# DorMouse.net
KiCad netlist of a schematic drawn in EAGLE
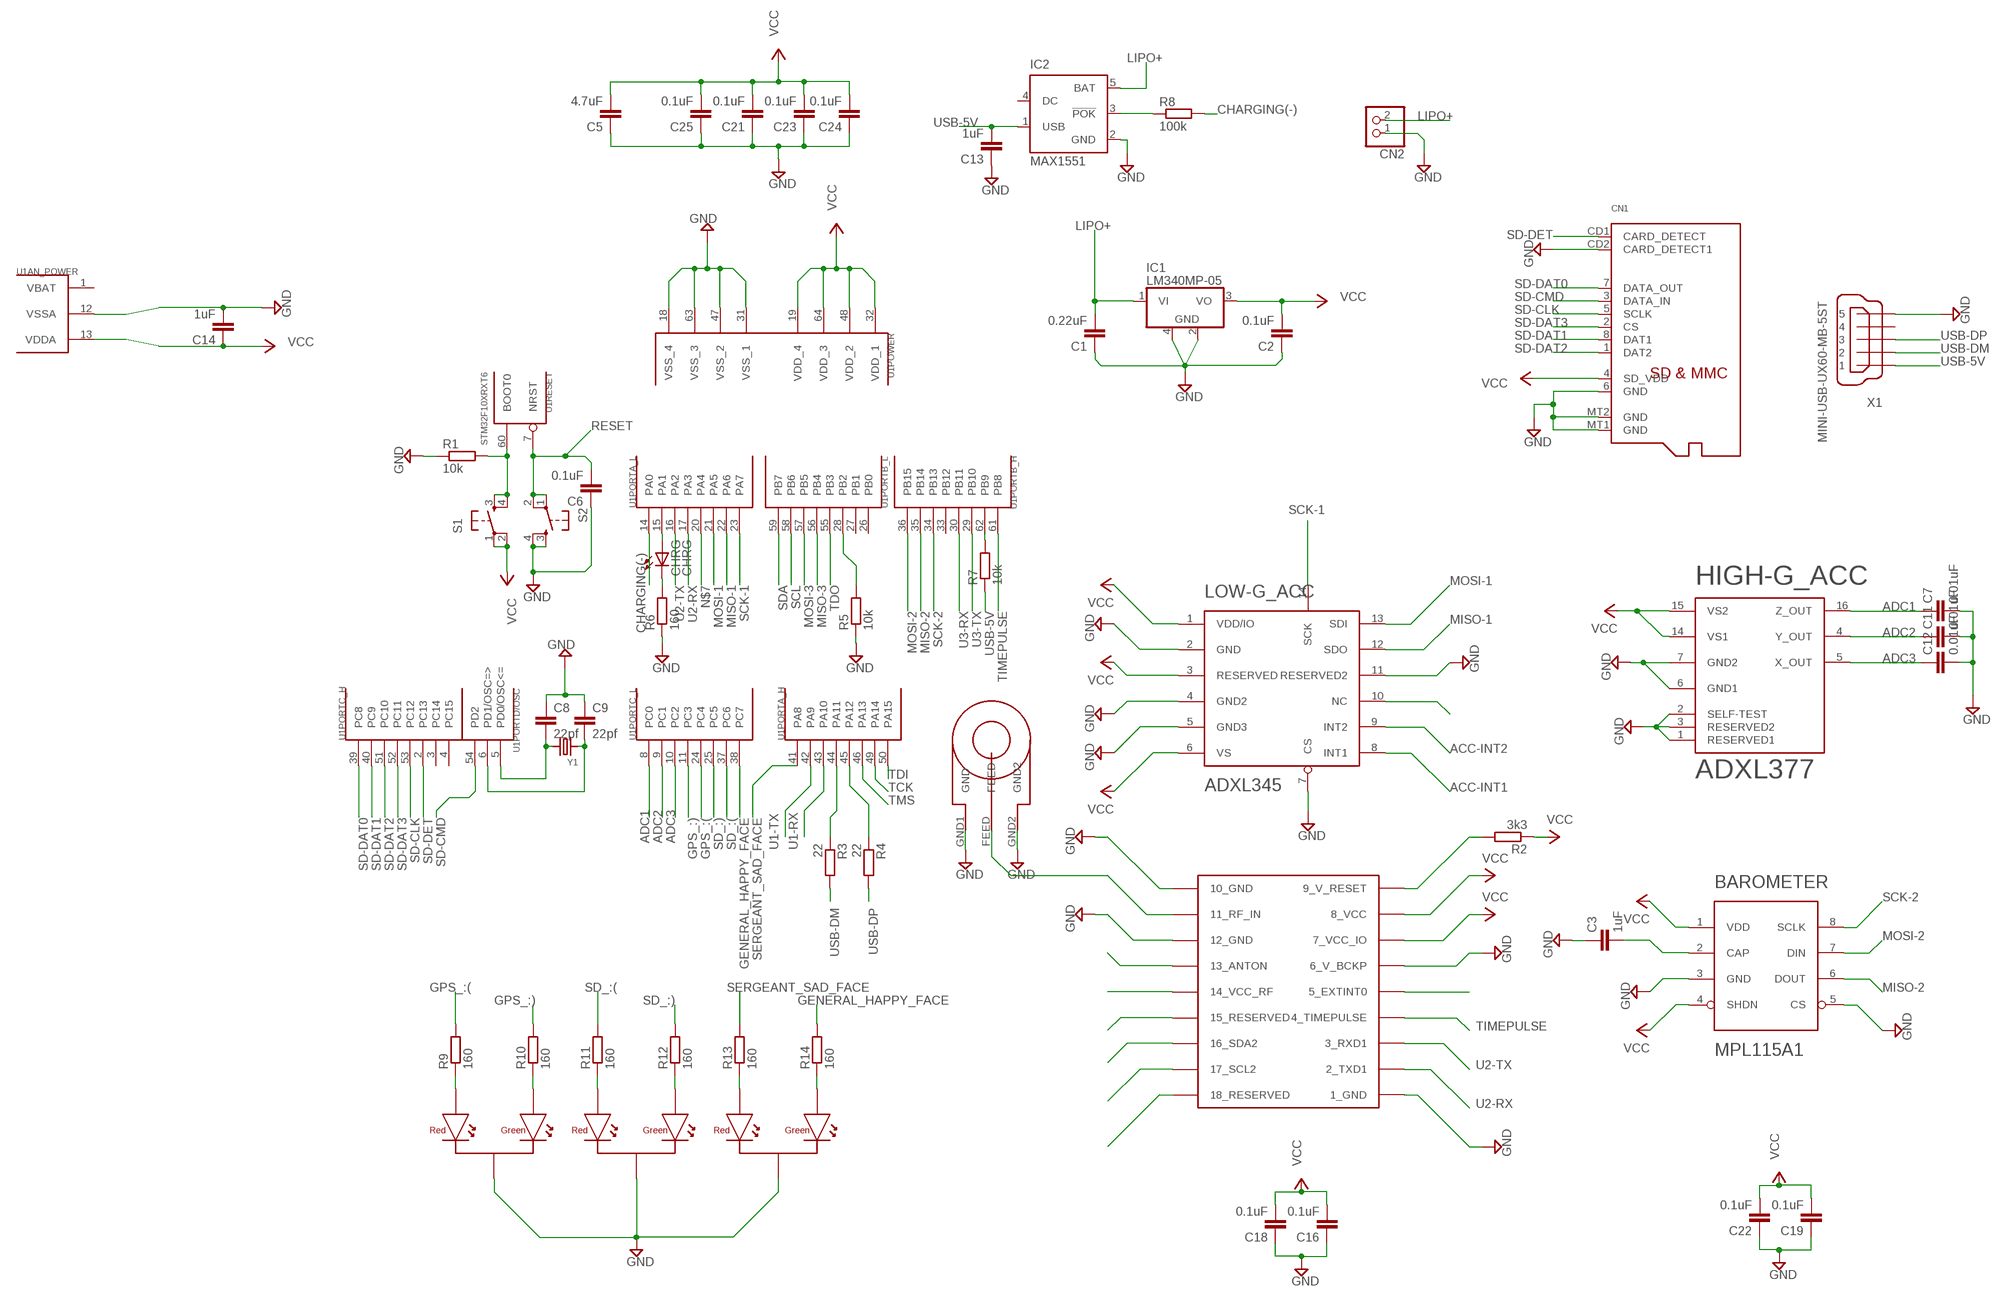
[diagram p0: schematic, sheet 1, part 1 of 2]
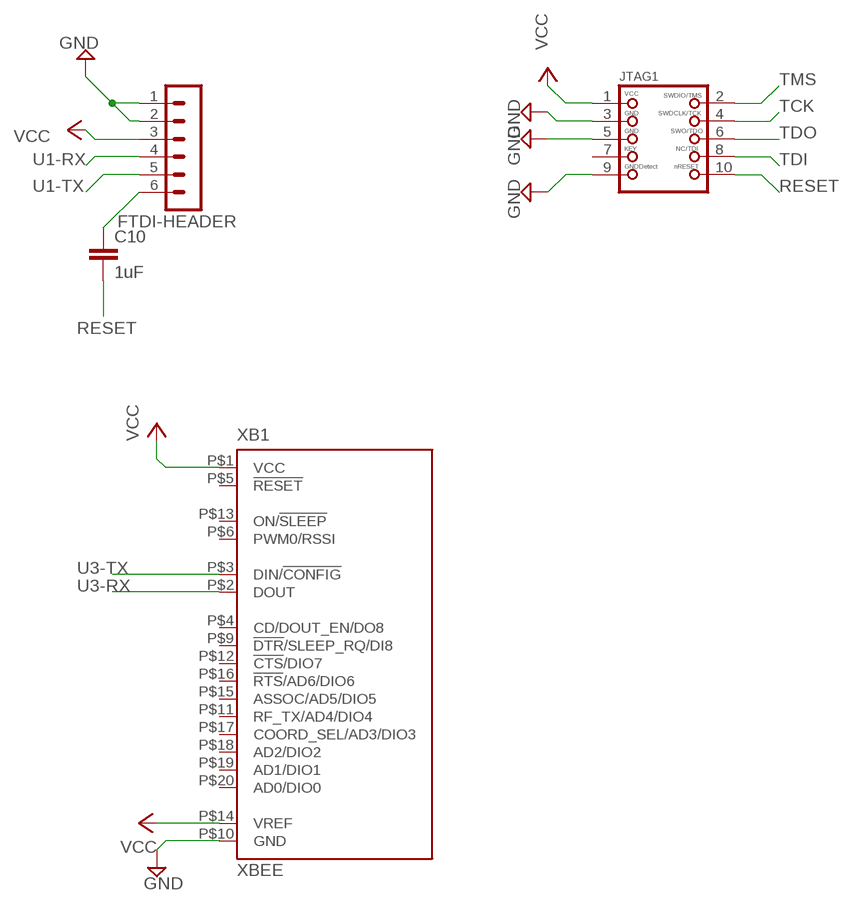
[diagram p1: schematic, sheet 1, part 2 of 2]

(export (version "E")
  (design (tool "Eeschema 10.0.6"))
  (components
    (comp (ref "BAROMETER")
      (value "MPL115A1")
      (footprint "eagle-import:LGA-8")
      (libsource (lib "eagle-import") (part "MPL115A1"))
    )
    (comp (ref "C1")
      (value "0.22uF")
      (footprint "eagle-import:C0402")
      (libsource (lib "eagle-import") (part "C-EUC0402"))
    )
    (comp (ref "C2")
      (value "0.1uF")
      (footprint "eagle-import:C0402")
      (libsource (lib "eagle-import") (part "C-EUC0402"))
    )
    (comp (ref "C3")
      (value "1uF")
      (footprint "eagle-import:C0402")
      (libsource (lib "eagle-import") (part "C-EUC0402"))
    )
    (comp (ref "C5")
      (value "4.7uF")
      (footprint "eagle-import:C0402")
      (libsource (lib "eagle-import") (part "C-EUC0402"))
    )
    (comp (ref "C6")
      (value "0.1uF")
      (footprint "eagle-import:C0402")
      (libsource (lib "eagle-import") (part "C-EUC0402"))
    )
    (comp (ref "C7")
      (value "0.01uF")
      (footprint "eagle-import:C0402")
      (libsource (lib "eagle-import") (part "C-EUC0402"))
    )
    (comp (ref "C8")
      (value "22pf")
      (footprint "eagle-import:C0402")
      (libsource (lib "eagle-import") (part "C-EUC0402"))
    )
    (comp (ref "C9")
      (value "22pf")
      (footprint "eagle-import:C0402")
      (libsource (lib "eagle-import") (part "C-EUC0402"))
    )
    (comp (ref "C10")
      (value "1uF")
      (footprint "eagle-import:C0402")
      (libsource (lib "eagle-import") (part "C-EUC0402"))
    )
    (comp (ref "C11")
      (value "0.01uF")
      (footprint "eagle-import:C0402")
      (libsource (lib "eagle-import") (part "C-EUC0402"))
    )
    (comp (ref "C12")
      (value "0.01uF")
      (footprint "eagle-import:C0402")
      (libsource (lib "eagle-import") (part "C-EUC0402"))
    )
    (comp (ref "C13")
      (value "1uF")
      (footprint "eagle-import:C0402")
      (libsource (lib "eagle-import") (part "C-EUC0402"))
    )
    (comp (ref "C14")
      (value "1uF")
      (footprint "eagle-import:C0402")
      (libsource (lib "eagle-import") (part "C-EUC0402"))
    )
    (comp (ref "C16")
      (value "0.1uF")
      (footprint "eagle-import:C0402")
      (libsource (lib "eagle-import") (part "C-EUC0402"))
    )
    (comp (ref "C18")
      (value "0.1uF")
      (footprint "eagle-import:C0402")
      (libsource (lib "eagle-import") (part "C-EUC0402"))
    )
    (comp (ref "C19")
      (value "0.1uF")
      (footprint "eagle-import:C0402")
      (libsource (lib "eagle-import") (part "C-EUC0402"))
    )
    (comp (ref "C21")
      (value "0.1uF")
      (footprint "eagle-import:C0402")
      (libsource (lib "eagle-import") (part "C-EUC0402"))
    )
    (comp (ref "C22")
      (value "0.1uF")
      (footprint "eagle-import:C0402")
      (libsource (lib "eagle-import") (part "C-EUC0402"))
    )
    (comp (ref "C23")
      (value "0.1uF")
      (footprint "eagle-import:C0402")
      (libsource (lib "eagle-import") (part "C-EUC0402"))
    )
    (comp (ref "C24")
      (value "0.1uF")
      (footprint "eagle-import:C0402")
      (libsource (lib "eagle-import") (part "C-EUC0402"))
    )
    (comp (ref "C25")
      (value "0.1uF")
      (footprint "eagle-import:C0402")
      (libsource (lib "eagle-import") (part "C-EUC0402"))
    )
    (comp (ref "CHRG")
      (value "CHRG")
      (footprint "eagle-import:CHIPLED_0603")
      (libsource (lib "eagle-import") (part "LEDCHIPLED_0603"))
    )
    (comp (ref "CN1")
      (value "MICROSD")
      (footprint "eagle-import:MICROSD")
      (libsource (lib "eagle-import") (part "MICROSD"))
    )
    (comp (ref "CN2")
      (value "JST_2PINSH2")
      (footprint "eagle-import:JSTSH2")
      (libsource (lib "eagle-import") (part "JST_2PINSH2"))
    )
    (comp (ref "FTDI-HEADER")
      (value "MA06-1")
      (footprint "eagle-import:MA06-1")
      (libsource (lib "eagle-import") (part "MA06-1"))
    )
    (comp (ref "GENERAL")
      (value "Status")
      (footprint "eagle-import:SOT23")
      (libsource (lib "eagle-import") (part "RED-GREEN_LED"))
    )
    (comp (ref "GPS")
      (value "UBLOX_MAX-6")
      (footprint "eagle-import:UBLOX_MAX-6")
      (libsource (lib "eagle-import") (part "UBLOX_MAX-6"))
    )
    (comp (ref "GPS-LED")
      (value "GPS")
      (footprint "eagle-import:SOT23")
      (libsource (lib "eagle-import") (part "RED-GREEN_LED"))
    )
    (comp (ref "HIGH-G_ACC")
      (value "ADXL377")
      (footprint "eagle-import:LFCSP-16")
      (libsource (lib "eagle-import") (part "ADXL377"))
    )
    (comp (ref "IC1")
      (value "LM340MP-05")
      (footprint "eagle-import:SOT223")
      (libsource (lib "eagle-import") (part "LM340?-MP05"))
    )
    (comp (ref "IC2")
      (value "MAX1551")
      (footprint "eagle-import:SOT23-5L")
      (fields (field (name "MF") "MAXIM") (field (name "MPN") "MAX1551EZK-T"))
      (libsource (lib "eagle-import") (part "MAX1551"))
    )
    (comp (ref "JTAG1")
      (value "JTAG-CORTEXM3")
      (footprint "eagle-import:2X05_1.27MM_SMT")
      (libsource (lib "eagle-import") (part "JTAG-CORTEXM3"))
    )
    (comp (ref "LOW-G_ACC")
      (value "ADXL345")
      (footprint "eagle-import:LGA-14")
      (libsource (lib "eagle-import") (part "ADXL345"))
    )
    (comp (ref "R1")
      (value "10k")
      (footprint "eagle-import:R0402")
      (libsource (lib "eagle-import") (part "R-EU_R0402"))
    )
    (comp (ref "R2")
      (value "3k3")
      (footprint "eagle-import:R0402")
      (libsource (lib "eagle-import") (part "R-EU_R0402"))
    )
    (comp (ref "R3")
      (value "22")
      (footprint "eagle-import:R0402")
      (libsource (lib "eagle-import") (part "R-EU_R0402"))
    )
    (comp (ref "R4")
      (value "22")
      (footprint "eagle-import:R0402")
      (libsource (lib "eagle-import") (part "R-EU_R0402"))
    )
    (comp (ref "R5")
      (value "10k")
      (footprint "eagle-import:R0402")
      (libsource (lib "eagle-import") (part "R-EU_R0402"))
    )
    (comp (ref "R6")
      (value "160")
      (footprint "eagle-import:R0402")
      (libsource (lib "eagle-import") (part "R-EU_R0402"))
    )
    (comp (ref "R7")
      (value "10k")
      (footprint "eagle-import:R0402")
      (libsource (lib "eagle-import") (part "R-EU_R0402"))
    )
    (comp (ref "R8")
      (value "100k")
      (footprint "eagle-import:R0402")
      (libsource (lib "eagle-import") (part "R-EU_R0402"))
    )
    (comp (ref "R9")
      (value "160")
      (footprint "eagle-import:R0402")
      (libsource (lib "eagle-import") (part "R-EU_R0402"))
    )
    (comp (ref "R10")
      (value "160")
      (footprint "eagle-import:R0402")
      (libsource (lib "eagle-import") (part "R-EU_R0402"))
    )
    (comp (ref "R11")
      (value "160")
      (footprint "eagle-import:R0402")
      (libsource (lib "eagle-import") (part "R-EU_R0402"))
    )
    (comp (ref "R12")
      (value "160")
      (footprint "eagle-import:R0402")
      (libsource (lib "eagle-import") (part "R-EU_R0402"))
    )
    (comp (ref "R13")
      (value "160")
      (footprint "eagle-import:R0402")
      (libsource (lib "eagle-import") (part "R-EU_R0402"))
    )
    (comp (ref "R14")
      (value "160")
      (footprint "eagle-import:R0402")
      (libsource (lib "eagle-import") (part "R-EU_R0402"))
    )
    (comp (ref "S1")
      (value "TAC_SWITCHSMD")
      (footprint "eagle-import:TACTILE_SWITCH_SMD")
      (libsource (lib "eagle-import") (part "TAC_SWITCHSMD"))
    )
    (comp (ref "S2")
      (value "TAC_SWITCHSMD")
      (footprint "eagle-import:TACTILE_SWITCH_SMD")
      (libsource (lib "eagle-import") (part "TAC_SWITCHSMD"))
    )
    (comp (ref "SD-LED")
      (value "SD-C")
      (footprint "eagle-import:SOT23")
      (libsource (lib "eagle-import") (part "RED-GREEN_LED"))
    )
    (comp (ref "U$1")
      (value "SARANTEL-SR1202")
      (footprint "eagle-import:SARANTEL-SR1202")
      (libsource (lib "eagle-import") (part "SARANTEL-SR1202"))
    )
    (comp (ref "U1")
      (value "STM32F10XRXT6")
      (footprint "eagle-import:TQFP64")
      (libsource (lib "eagle-import") (part "STM32F10XRXT6"))
    )
    (comp (ref "X1")
      (value "MINI-USB-UX60-MB-5ST")
      (footprint "eagle-import:UX60-MB-5ST")
      (libsource (lib "eagle-import") (part "MINI-USB-UX60-MB-5ST"))
    )
    (comp (ref "XB1")
      (value "XBEE")
      (footprint "eagle-import:XBEE")
      (fields (field (name "MPN") "XBP24-Z7UIT-004"))
      (libsource (lib "eagle-import") (part "XBEE"))
    )
    (comp (ref "Y1")
      (value "CRYSTALSMD")
      (footprint "eagle-import:HC49UP")
      (libsource (lib "eagle-import") (part "CRYSTALSMD"))
    )
  )
  (nets
    (net (code "1") (name "/ACC-INT1") (class "Default")
      (node (ref "LOW-G_ACC") (pin "8") (pinfunction "INT1_8") (pintype "bidirectional"))
    )
    (net (code "2") (name "/ACC-INT2") (class "Default")
      (node (ref "LOW-G_ACC") (pin "9") (pinfunction "INT2_9") (pintype "bidirectional"))
    )
    (net (code "3") (name "/ADC1") (class "Default")
      (node (ref "C7") (pin "1") (pinfunction "1_1") (pintype "passive"))
      (node (ref "HIGH-G_ACC") (pin "16") (pinfunction "Z_OUT_16") (pintype "bidirectional"))
      (node (ref "U1") (pin "8") (pinfunction "PC0_8") (pintype "bidirectional"))
    )
    (net (code "4") (name "/ADC2") (class "Default")
      (node (ref "C11") (pin "1") (pinfunction "1_1") (pintype "passive"))
      (node (ref "HIGH-G_ACC") (pin "4") (pinfunction "Y_OUT_4") (pintype "bidirectional"))
      (node (ref "U1") (pin "9") (pinfunction "PC1_9") (pintype "bidirectional"))
    )
    (net (code "5") (name "/ADC3") (class "Default")
      (node (ref "C12") (pin "1") (pinfunction "1_1") (pintype "passive"))
      (node (ref "HIGH-G_ACC") (pin "5") (pinfunction "X_OUT_5") (pintype "bidirectional"))
      (node (ref "U1") (pin "10") (pinfunction "PC2_10") (pintype "bidirectional"))
    )
    (net (code "6") (name "/CHARGING(-)") (class "Default")
      (node (ref "R8") (pin "2") (pinfunction "2_2") (pintype "passive"))
      (node (ref "U1") (pin "14") (pinfunction "PA0_14") (pintype "bidirectional"))
    )
    (net (code "7") (name "/GENERAL_HAPPY_FACE") (class "Default")
      (node (ref "R14") (pin "2") (pinfunction "2_2") (pintype "passive"))
      (node (ref "U1") (pin "38") (pinfunction "PC7_38") (pintype "bidirectional"))
    )
    (net (code "8") (name "/GPS_:(") (class "Default")
      (node (ref "R9") (pin "2") (pinfunction "2_2") (pintype "passive"))
      (node (ref "U1") (pin "24") (pinfunction "PC4_24") (pintype "bidirectional"))
    )
    (net (code "9") (name "/GPS_:)") (class "Default")
      (node (ref "R10") (pin "2") (pinfunction "2_2") (pintype "passive"))
      (node (ref "U1") (pin "11") (pinfunction "PC3_11") (pintype "bidirectional"))
    )
    (net (code "10") (name "/LIPO+") (class "Default")
      (node (ref "C1") (pin "2") (pinfunction "2_2") (pintype "passive"))
      (node (ref "CN2") (pin "2") (pinfunction "2_2") (pintype "passive"))
      (node (ref "IC1") (pin "1") (pinfunction "VI_1") (pintype "input"))
      (node (ref "IC2") (pin "5") (pinfunction "BAT_5") (pintype "passive"))
    )
    (net (code "11") (name "/MISO-1") (class "Default")
      (node (ref "LOW-G_ACC") (pin "12") (pinfunction "SDO_12") (pintype "bidirectional"))
      (node (ref "U1") (pin "22") (pinfunction "PA6_22") (pintype "bidirectional"))
    )
    (net (code "12") (name "/MISO-2") (class "Default")
      (node (ref "BAROMETER") (pin "6") (pinfunction "DOUT_6") (pintype "bidirectional"))
      (node (ref "U1") (pin "35") (pinfunction "PB14_35") (pintype "bidirectional"))
    )
    (net (code "13") (name "/MISO-3") (class "Default")
      (node (ref "U1") (pin "56") (pinfunction "PB4_56") (pintype "bidirectional"))
    )
    (net (code "14") (name "/MOSI-1") (class "Default")
      (node (ref "LOW-G_ACC") (pin "13") (pinfunction "SDI_13") (pintype "bidirectional"))
      (node (ref "U1") (pin "21") (pinfunction "PA5_21") (pintype "bidirectional"))
    )
    (net (code "15") (name "/MOSI-2") (class "Default")
      (node (ref "BAROMETER") (pin "7") (pinfunction "DIN_7") (pintype "bidirectional"))
      (node (ref "U1") (pin "36") (pinfunction "PB15_36") (pintype "bidirectional"))
    )
    (net (code "16") (name "/MOSI-3") (class "Default")
      (node (ref "U1") (pin "57") (pinfunction "PB5_57") (pintype "bidirectional"))
    )
    (net (code "17") (name "/N$7") (class "Default")
      (node (ref "U1") (pin "20") (pinfunction "PA4_20") (pintype "bidirectional"))
    )
    (net (code "18") (name "/RESET") (class "Default")
      (node (ref "C10") (pin "2") (pinfunction "2_2") (pintype "passive"))
      (node (ref "C6") (pin "2") (pinfunction "2_2") (pintype "passive"))
      (node (ref "JTAG1") (pin "10") (pinfunction "10_10") (pintype "passive"))
      (node (ref "S2") (pin "1") (pinfunction "1_1") (pintype "passive"))
      (node (ref "S2") (pin "2") (pinfunction "2_2") (pintype "passive"))
      (node (ref "U1") (pin "7") (pinfunction "NRST_7") (pintype "input"))
    )
    (net (code "19") (name "/SCK-1") (class "Default")
      (node (ref "LOW-G_ACC") (pin "14") (pinfunction "SCK_14") (pintype "bidirectional"))
      (node (ref "U1") (pin "23") (pinfunction "PA7_23") (pintype "bidirectional"))
    )
    (net (code "20") (name "/SCK-2") (class "Default")
      (node (ref "BAROMETER") (pin "8") (pinfunction "SCLK_8") (pintype "bidirectional"))
      (node (ref "U1") (pin "34") (pinfunction "PB13_34") (pintype "bidirectional"))
    )
    (net (code "21") (name "/SCL") (class "Default")
      (node (ref "U1") (pin "58") (pinfunction "PB6_58") (pintype "bidirectional"))
    )
    (net (code "22") (name "/SD-CLK") (class "Default")
      (node (ref "CN1") (pin "5") (pinfunction "SCLK_5") (pintype "input"))
      (node (ref "U1") (pin "53") (pinfunction "PC12_53") (pintype "bidirectional"))
    )
    (net (code "23") (name "/SD-CMD") (class "Default")
      (node (ref "CN1") (pin "3") (pinfunction "DATA_IN_3") (pintype "input"))
      (node (ref "U1") (pin "54") (pinfunction "PD2_54") (pintype "bidirectional"))
    )
    (net (code "24") (name "/SD-DAT0") (class "Default")
      (node (ref "CN1") (pin "7") (pinfunction "DATA_OUT_7") (pintype "output"))
      (node (ref "U1") (pin "39") (pinfunction "PC8_39") (pintype "bidirectional"))
    )
    (net (code "25") (name "/SD-DAT1") (class "Default")
      (node (ref "CN1") (pin "8") (pinfunction "DAT1_8") (pintype "bidirectional"))
      (node (ref "U1") (pin "40") (pinfunction "PC9_40") (pintype "bidirectional"))
    )
    (net (code "26") (name "/SD-DAT2") (class "Default")
      (node (ref "CN1") (pin "1") (pinfunction "DAT2_1") (pintype "bidirectional"))
      (node (ref "U1") (pin "51") (pinfunction "PC10_51") (pintype "bidirectional"))
    )
    (net (code "27") (name "/SD-DAT3") (class "Default")
      (node (ref "CN1") (pin "2") (pinfunction "CS_2") (pintype "input"))
      (node (ref "U1") (pin "52") (pinfunction "PC11_52") (pintype "bidirectional"))
    )
    (net (code "28") (name "/SD-DET") (class "Default")
      (node (ref "CN1") (pin "CD1") (pinfunction "CARD_DETECT_CD1") (pintype "passive"))
      (node (ref "U1") (pin "2") (pinfunction "PC13_2") (pintype "bidirectional"))
    )
    (net (code "29") (name "/SDA") (class "Default")
      (node (ref "U1") (pin "59") (pinfunction "PB7_59") (pintype "bidirectional"))
    )
    (net (code "30") (name "/SD_:(") (class "Default")
      (node (ref "R11") (pin "2") (pinfunction "2_2") (pintype "passive"))
      (node (ref "U1") (pin "37") (pinfunction "PC6_37") (pintype "bidirectional"))
    )
    (net (code "31") (name "/SD_:)") (class "Default")
      (node (ref "R12") (pin "2") (pinfunction "2_2") (pintype "passive"))
      (node (ref "U1") (pin "25") (pinfunction "PC5_25") (pintype "bidirectional"))
    )
    (net (code "32") (name "/SERGEANT_SAD_FACE") (class "Default")
      (node (ref "R13") (pin "2") (pinfunction "2_2") (pintype "passive"))
      (node (ref "U1") (pin "41") (pinfunction "PA8_41") (pintype "bidirectional"))
    )
    (net (code "33") (name "/TCK") (class "Default")
      (node (ref "JTAG1") (pin "4") (pinfunction "4_4") (pintype "passive"))
      (node (ref "U1") (pin "49") (pinfunction "PA14_49") (pintype "bidirectional"))
    )
    (net (code "34") (name "/TDI") (class "Default")
      (node (ref "JTAG1") (pin "8") (pinfunction "8_8") (pintype "passive"))
      (node (ref "U1") (pin "50") (pinfunction "PA15_50") (pintype "bidirectional"))
    )
    (net (code "35") (name "/TDO") (class "Default")
      (node (ref "JTAG1") (pin "6") (pinfunction "6_6") (pintype "passive"))
      (node (ref "U1") (pin "55") (pinfunction "PB3_55") (pintype "bidirectional"))
    )
    (net (code "36") (name "/TIMEPULSE") (class "Default")
      (node (ref "GPS") (pin "4_TIMEPULSE") (pinfunction "4_TIMEPULSE_4_TIMEPULSE") (pintype "bidirectional"))
      (node (ref "U1") (pin "61") (pinfunction "PB8_61") (pintype "bidirectional"))
    )
    (net (code "37") (name "/TMS") (class "Default")
      (node (ref "JTAG1") (pin "2") (pinfunction "2_2") (pintype "passive"))
      (node (ref "U1") (pin "46") (pinfunction "PA13_46") (pintype "bidirectional"))
    )
    (net (code "38") (name "/U1-RX") (class "Default")
      (node (ref "FTDI-HEADER") (pin "4") (pinfunction "4_4") (pintype "passive"))
      (node (ref "U1") (pin "43") (pinfunction "PA10_43") (pintype "bidirectional"))
    )
    (net (code "39") (name "/U1-TX") (class "Default")
      (node (ref "FTDI-HEADER") (pin "5") (pinfunction "5_5") (pintype "passive"))
      (node (ref "U1") (pin "42") (pinfunction "PA9_42") (pintype "bidirectional"))
    )
    (net (code "40") (name "/U2-RX") (class "Default")
      (node (ref "GPS") (pin "2_TXD1") (pinfunction "2_TXD1_2_TXD1") (pintype "bidirectional"))
      (node (ref "U1") (pin "17") (pinfunction "PA3_17") (pintype "bidirectional"))
    )
    (net (code "41") (name "/U2-TX") (class "Default")
      (node (ref "GPS") (pin "3_RXD1") (pinfunction "3_RXD1_3_RXD1") (pintype "bidirectional"))
      (node (ref "U1") (pin "16") (pinfunction "PA2_16") (pintype "bidirectional"))
    )
    (net (code "42") (name "/U3-RX") (class "Default")
      (node (ref "U1") (pin "30") (pinfunction "PB11_30") (pintype "bidirectional"))
      (node (ref "XB1") (pin "P$2") (pinfunction "DOUT_P$2") (pintype "output"))
    )
    (net (code "43") (name "/U3-TX") (class "Default")
      (node (ref "U1") (pin "29") (pinfunction "PB10_29") (pintype "bidirectional"))
      (node (ref "XB1") (pin "P$3") (pinfunction "DIN/~{CONFIG}_P$3") (pintype "input"))
    )
    (net (code "44") (name "/USB-5V") (class "Default")
      (node (ref "C13") (pin "2") (pinfunction "2_2") (pintype "passive"))
      (node (ref "IC2") (pin "1") (pinfunction "USB_1") (pintype "input"))
      (node (ref "R7") (pin "1") (pinfunction "1_1") (pintype "passive"))
      (node (ref "X1") (pin "1") (pinfunction "1_1") (pintype "input"))
    )
    (net (code "45") (name "/USB-DM") (class "Default")
      (node (ref "R3") (pin "2") (pinfunction "2_2") (pintype "passive"))
      (node (ref "X1") (pin "2") (pinfunction "2_2") (pintype "input"))
    )
    (net (code "46") (name "/USB-DP") (class "Default")
      (node (ref "R4") (pin "2") (pinfunction "2_2") (pintype "passive"))
      (node (ref "X1") (pin "3") (pinfunction "3_3") (pintype "input"))
    )
    (net (code "47") (name "/VBAT") (class "Default")
      (node (ref "U1") (pin "1") (pinfunction "VBAT_1") (pintype "power_in"))
    )
    (net (code "48") (name "GND") (class "Default")
      (node (ref "BAROMETER") (pin "3") (pinfunction "GND_3") (pintype "bidirectional"))
      (node (ref "BAROMETER") (pin "5") (pinfunction "CS_5") (pintype "bidirectional"))
      (node (ref "C1") (pin "1") (pinfunction "1_1") (pintype "passive"))
      (node (ref "C11") (pin "2") (pinfunction "2_2") (pintype "passive"))
      (node (ref "C12") (pin "2") (pinfunction "2_2") (pintype "passive"))
      (node (ref "C13") (pin "1") (pinfunction "1_1") (pintype "passive"))
      (node (ref "C14") (pin "2") (pinfunction "2_2") (pintype "passive"))
      (node (ref "C16") (pin "1") (pinfunction "1_1") (pintype "passive"))
      (node (ref "C18") (pin "1") (pinfunction "1_1") (pintype "passive"))
      (node (ref "C19") (pin "1") (pinfunction "1_1") (pintype "passive"))
      (node (ref "C2") (pin "1") (pinfunction "1_1") (pintype "passive"))
      (node (ref "C21") (pin "1") (pinfunction "1_1") (pintype "passive"))
      (node (ref "C22") (pin "1") (pinfunction "1_1") (pintype "passive"))
      (node (ref "C23") (pin "1") (pinfunction "1_1") (pintype "passive"))
      (node (ref "C24") (pin "1") (pinfunction "1_1") (pintype "passive"))
      (node (ref "C25") (pin "1") (pinfunction "1_1") (pintype "passive"))
      (node (ref "C3") (pin "1") (pinfunction "1_1") (pintype "passive"))
      (node (ref "C5") (pin "1") (pinfunction "1_1") (pintype "passive"))
      (node (ref "C6") (pin "1") (pinfunction "1_1") (pintype "passive"))
      (node (ref "C7") (pin "2") (pinfunction "2_2") (pintype "passive"))
      (node (ref "C8") (pin "1") (pinfunction "1_1") (pintype "passive"))
      (node (ref "C9") (pin "1") (pinfunction "1_1") (pintype "passive"))
      (node (ref "CN1") (pin "6") (pinfunction "GND_6") (pintype "power_in"))
      (node (ref "CN1") (pin "CD2") (pinfunction "CARD_DETECT1_CD2") (pintype "passive"))
      (node (ref "CN1") (pin "MT1") (pinfunction "GND_MT1") (pintype "power_in"))
      (node (ref "CN1") (pin "MT2") (pinfunction "GND_MT2") (pintype "power_in"))
      (node (ref "CN2") (pin "1") (pinfunction "1_1") (pintype "passive"))
      (node (ref "FTDI-HEADER") (pin "1") (pinfunction "1_1") (pintype "passive"))
      (node (ref "FTDI-HEADER") (pin "2") (pinfunction "2_2") (pintype "passive"))
      (node (ref "GENERAL") (pin "3") (pinfunction "CATHODE_3") (pintype "bidirectional"))
      (node (ref "GPS") (pin "10_GND") (pinfunction "10_GND_10_GND") (pintype "power_in"))
      (node (ref "GPS") (pin "12_GND") (pinfunction "12_GND_12_GND") (pintype "power_in"))
      (node (ref "GPS") (pin "1_GND") (pinfunction "1_GND_1_GND") (pintype "power_in"))
      (node (ref "GPS") (pin "6_V_BCKP") (pinfunction "6_V_BCKP_6_V_BCKP") (pintype "bidirectional"))
      (node (ref "GPS-LED") (pin "3") (pinfunction "CATHODE_3") (pintype "bidirectional"))
      (node (ref "HIGH-G_ACC") (pin "1") (pinfunction "RESERVED1_1") (pintype "bidirectional"))
      (node (ref "HIGH-G_ACC") (pin "2") (pinfunction "SELF-TEST_2") (pintype "bidirectional"))
      (node (ref "HIGH-G_ACC") (pin "3") (pinfunction "RESERVED2_3") (pintype "bidirectional"))
      (node (ref "HIGH-G_ACC") (pin "6") (pinfunction "GND1_6") (pintype "bidirectional"))
      (node (ref "HIGH-G_ACC") (pin "7") (pinfunction "GND2_7") (pintype "bidirectional"))
      (node (ref "IC1") (pin "2") (pinfunction "GND1_2") (pintype "passive"))
      (node (ref "IC1") (pin "4") (pinfunction "GND_4") (pintype "passive"))
      (node (ref "IC2") (pin "2") (pinfunction "GND_2") (pintype "power_in"))
      (node (ref "JTAG1") (pin "3") (pinfunction "3_3") (pintype "passive"))
      (node (ref "JTAG1") (pin "5") (pinfunction "5_5") (pintype "passive"))
      (node (ref "JTAG1") (pin "9") (pinfunction "9_9") (pintype "passive"))
      (node (ref "LOW-G_ACC") (pin "11") (pinfunction "RESERVED2_11") (pintype "bidirectional"))
      (node (ref "LOW-G_ACC") (pin "2") (pinfunction "GND_2") (pintype "bidirectional"))
      (node (ref "LOW-G_ACC") (pin "4") (pinfunction "GND2_4") (pintype "bidirectional"))
      (node (ref "LOW-G_ACC") (pin "5") (pinfunction "GND3_5") (pintype "bidirectional"))
      (node (ref "LOW-G_ACC") (pin "7") (pinfunction "CS_7") (pintype "bidirectional"))
      (node (ref "R1") (pin "1") (pinfunction "1_1") (pintype "passive"))
      (node (ref "R5") (pin "1") (pinfunction "1_1") (pintype "passive"))
      (node (ref "R6") (pin "1") (pinfunction "1_1") (pintype "passive"))
      (node (ref "S2") (pin "3") (pinfunction "3_3") (pintype "passive"))
      (node (ref "S2") (pin "4") (pinfunction "4_4") (pintype "passive"))
      (node (ref "SD-LED") (pin "3") (pinfunction "CATHODE_3") (pintype "bidirectional"))
      (node (ref "U$1") (pin "GND1") (pinfunction "GND_GND1") (pintype "bidirectional"))
      (node (ref "U$1") (pin "GND2") (pinfunction "GND2_GND2") (pintype "bidirectional"))
      (node (ref "U1") (pin "12") (pinfunction "VSSA_12") (pintype "power_in"))
      (node (ref "U1") (pin "18") (pinfunction "VSS_4_18") (pintype "power_in"))
      (node (ref "U1") (pin "31") (pinfunction "VSS_1_31") (pintype "power_in"))
      (node (ref "U1") (pin "47") (pinfunction "VSS_2_47") (pintype "power_in"))
      (node (ref "U1") (pin "63") (pinfunction "VSS_3_63") (pintype "power_in"))
      (node (ref "X1") (pin "5") (pinfunction "5_5") (pintype "input"))
      (node (ref "XB1") (pin "P$10") (pinfunction "GND_P$10") (pintype "power_in"))
    )
    (net (code "49") (name "Net-(BAROMETER-CAP)") (class "Default")
      (node (ref "BAROMETER") (pin "2") (pinfunction "CAP_2") (pintype "bidirectional"))
      (node (ref "C3") (pin "2") (pinfunction "2_2") (pintype "passive"))
    )
    (net (code "50") (name "Net-(C10-Pad1)") (class "Default")
      (node (ref "C10") (pin "1") (pinfunction "1_1") (pintype "passive"))
      (node (ref "FTDI-HEADER") (pin "6") (pinfunction "6_6") (pintype "passive"))
    )
    (net (code "51") (name "Net-(CHRG-PadC)") (class "Default")
      (node (ref "CHRG") (pin "C") (pinfunction "C_C") (pintype "passive"))
      (node (ref "R6") (pin "2") (pinfunction "2_2") (pintype "passive"))
    )
    (net (code "52") (name "Net-(GENERAL-GREEN-ANODE)") (class "Default")
      (node (ref "GENERAL") (pin "2") (pinfunction "GREEN-ANODE_2") (pintype "bidirectional"))
      (node (ref "R14") (pin "1") (pinfunction "1_1") (pintype "passive"))
    )
    (net (code "53") (name "Net-(GENERAL-RED-ANODE)") (class "Default")
      (node (ref "GENERAL") (pin "1") (pinfunction "RED-ANODE_1") (pintype "bidirectional"))
      (node (ref "R13") (pin "1") (pinfunction "1_1") (pintype "passive"))
    )
    (net (code "54") (name "Net-(GPS-LED-GREEN-ANODE)") (class "Default")
      (node (ref "GPS-LED") (pin "2") (pinfunction "GREEN-ANODE_2") (pintype "bidirectional"))
      (node (ref "R10") (pin "1") (pinfunction "1_1") (pintype "passive"))
    )
    (net (code "55") (name "Net-(GPS-LED-RED-ANODE)") (class "Default")
      (node (ref "GPS-LED") (pin "1") (pinfunction "RED-ANODE_1") (pintype "bidirectional"))
      (node (ref "R9") (pin "1") (pinfunction "1_1") (pintype "passive"))
    )
    (net (code "56") (name "Net-(GPS-Pad9_V_RESET)") (class "Default")
      (node (ref "GPS") (pin "9_V_RESET") (pinfunction "9_V_RESET_9_V_RESET") (pintype "power_in"))
      (node (ref "R2") (pin "2") (pinfunction "2_2") (pintype "passive"))
    )
    (net (code "57") (name "Net-(GPS-Pad11_RF_IN)") (class "Default")
      (node (ref "GPS") (pin "11_RF_IN") (pinfunction "11_RF_IN_11_RF_IN") (pintype "bidirectional"))
      (node (ref "U$1") (pin "FEED") (pinfunction "FEED_FEED") (pintype "bidirectional"))
    )
    (net (code "58") (name "Net-(IC2-~{POK})") (class "Default")
      (node (ref "IC2") (pin "3") (pinfunction "~{POK}_3") (pintype "output"))
      (node (ref "R8") (pin "1") (pinfunction "1_1") (pintype "passive"))
    )
    (net (code "59") (name "Net-(SD-LED-GREEN-ANODE)") (class "Default")
      (node (ref "R12") (pin "1") (pinfunction "1_1") (pintype "passive"))
      (node (ref "SD-LED") (pin "2") (pinfunction "GREEN-ANODE_2") (pintype "bidirectional"))
    )
    (net (code "60") (name "Net-(SD-LED-RED-ANODE)") (class "Default")
      (node (ref "R11") (pin "1") (pinfunction "1_1") (pintype "passive"))
      (node (ref "SD-LED") (pin "1") (pinfunction "RED-ANODE_1") (pintype "bidirectional"))
    )
    (net (code "61") (name "Net-(U1B-PA11)") (class "Default")
      (node (ref "R3") (pin "1") (pinfunction "1_1") (pintype "passive"))
      (node (ref "U1") (pin "44") (pinfunction "PA11_44") (pintype "bidirectional"))
    )
    (net (code "62") (name "Net-(U1B-PA12)") (class "Default")
      (node (ref "R4") (pin "1") (pinfunction "1_1") (pintype "passive"))
      (node (ref "U1") (pin "45") (pinfunction "PA12_45") (pintype "bidirectional"))
    )
    (net (code "63") (name "Net-(U1C-PA1)") (class "Default")
      (node (ref "CHRG") (pin "A") (pinfunction "A_A") (pintype "passive"))
      (node (ref "U1") (pin "15") (pinfunction "PA1_15") (pintype "bidirectional"))
    )
    (net (code "64") (name "Net-(U1D-PB9)") (class "Default")
      (node (ref "R7") (pin "2") (pinfunction "2_2") (pintype "passive"))
      (node (ref "U1") (pin "62") (pinfunction "PB9_62") (pintype "bidirectional"))
    )
    (net (code "65") (name "Net-(U1E-PB2)") (class "Default")
      (node (ref "R5") (pin "2") (pinfunction "2_2") (pintype "passive"))
      (node (ref "U1") (pin "28") (pinfunction "PB2_28") (pintype "bidirectional"))
    )
    (net (code "66") (name "Net-(U1H-PD0{slash}OSC<=)") (class "Default")
      (node (ref "C8") (pin "2") (pinfunction "2_2") (pintype "passive"))
      (node (ref "U1") (pin "5") (pinfunction "PD0/OSC<=_5") (pintype "bidirectional"))
      (node (ref "Y1") (pin "2") (pinfunction "2_2") (pintype "passive"))
    )
    (net (code "67") (name "Net-(U1H-PD1{slash}OSC=>)") (class "Default")
      (node (ref "C9") (pin "2") (pinfunction "2_2") (pintype "passive"))
      (node (ref "U1") (pin "6") (pinfunction "PD1/OSC=>_6") (pintype "bidirectional"))
      (node (ref "Y1") (pin "1") (pinfunction "1_1") (pintype "passive"))
    )
    (net (code "68") (name "Net-(U1J-BOOT0)") (class "Default")
      (node (ref "R1") (pin "2") (pinfunction "2_2") (pintype "passive"))
      (node (ref "S1") (pin "3") (pinfunction "3_3") (pintype "passive"))
      (node (ref "S1") (pin "4") (pinfunction "4_4") (pintype "passive"))
      (node (ref "U1") (pin "60") (pinfunction "BOOT0_60") (pintype "input"))
    )
    (net (code "69") (name "VCC") (class "Default")
      (node (ref "BAROMETER") (pin "1") (pinfunction "VDD_1") (pintype "bidirectional"))
      (node (ref "BAROMETER") (pin "4") (pinfunction "SHDN_4") (pintype "bidirectional"))
      (node (ref "C14") (pin "1") (pinfunction "1_1") (pintype "passive"))
      (node (ref "C16") (pin "2") (pinfunction "2_2") (pintype "passive"))
      (node (ref "C18") (pin "2") (pinfunction "2_2") (pintype "passive"))
      (node (ref "C19") (pin "2") (pinfunction "2_2") (pintype "passive"))
      (node (ref "C2") (pin "2") (pinfunction "2_2") (pintype "passive"))
      (node (ref "C21") (pin "2") (pinfunction "2_2") (pintype "passive"))
      (node (ref "C22") (pin "2") (pinfunction "2_2") (pintype "passive"))
      (node (ref "C23") (pin "2") (pinfunction "2_2") (pintype "passive"))
      (node (ref "C24") (pin "2") (pinfunction "2_2") (pintype "passive"))
      (node (ref "C25") (pin "2") (pinfunction "2_2") (pintype "passive"))
      (node (ref "C5") (pin "2") (pinfunction "2_2") (pintype "passive"))
      (node (ref "CN1") (pin "4") (pinfunction "SD_VDD_4") (pintype "power_in"))
      (node (ref "FTDI-HEADER") (pin "3") (pinfunction "3_3") (pintype "passive"))
      (node (ref "GPS") (pin "7_VCC_IO") (pinfunction "7_VCC_IO_7_VCC_IO") (pintype "power_in"))
      (node (ref "GPS") (pin "8_VCC") (pinfunction "8_VCC_8_VCC") (pintype "power_in"))
      (node (ref "HIGH-G_ACC") (pin "14") (pinfunction "VS1_14") (pintype "bidirectional"))
      (node (ref "HIGH-G_ACC") (pin "15") (pinfunction "VS2_15") (pintype "bidirectional"))
      (node (ref "IC1") (pin "3") (pinfunction "VO_3") (pintype "passive"))
      (node (ref "JTAG1") (pin "1") (pinfunction "1_1") (pintype "passive"))
      (node (ref "LOW-G_ACC") (pin "1") (pinfunction "VDD/IO_1") (pintype "bidirectional"))
      (node (ref "LOW-G_ACC") (pin "3") (pinfunction "RESERVED_3") (pintype "bidirectional"))
      (node (ref "LOW-G_ACC") (pin "6") (pinfunction "VS_6") (pintype "bidirectional"))
      (node (ref "R2") (pin "1") (pinfunction "1_1") (pintype "passive"))
      (node (ref "S1") (pin "1") (pinfunction "1_1") (pintype "passive"))
      (node (ref "S1") (pin "2") (pinfunction "2_2") (pintype "passive"))
      (node (ref "U1") (pin "13") (pinfunction "VDDA_13") (pintype "power_in"))
      (node (ref "U1") (pin "19") (pinfunction "VDD_4_19") (pintype "power_in"))
      (node (ref "U1") (pin "32") (pinfunction "VDD_1_32") (pintype "power_in"))
      (node (ref "U1") (pin "48") (pinfunction "VDD_2_48") (pintype "power_in"))
      (node (ref "U1") (pin "64") (pinfunction "VDD_3_64") (pintype "power_in"))
      (node (ref "XB1") (pin "P$1") (pinfunction "VCC_P$1") (pintype "power_in"))
      (node (ref "XB1") (pin "P$14") (pinfunction "VREF_P$14") (pintype "input"))
    )
    (net (code "70") (name "unconnected-(GPS-Pad5_EXTINT0)") (class "Default")
      (node (ref "GPS") (pin "5_EXTINT0") (pinfunction "5_EXTINT0_5_EXTINT0") (pintype "bidirectional"))
    )
    (net (code "71") (name "unconnected-(GPS-Pad13_ANTON)") (class "Default")
      (node (ref "GPS") (pin "13_ANTON") (pinfunction "13_ANTON_13_ANTON") (pintype "bidirectional"))
    )
    (net (code "72") (name "unconnected-(GPS-Pad14_VCC_RF)") (class "Default")
      (node (ref "GPS") (pin "14_VCC_RF") (pinfunction "14_VCC_RF_14_VCC_RF") (pintype "bidirectional"))
    )
    (net (code "73") (name "unconnected-(GPS-Pad15_RESERVED)") (class "Default")
      (node (ref "GPS") (pin "15_RESERVED") (pinfunction "15_RESERVED_15_RESERVED") (pintype "bidirectional"))
    )
    (net (code "74") (name "unconnected-(GPS-Pad16_SDA2)") (class "Default")
      (node (ref "GPS") (pin "16_SDA2") (pinfunction "16_SDA2_16_SDA2") (pintype "bidirectional"))
    )
    (net (code "75") (name "unconnected-(GPS-Pad17_SCL2)") (class "Default")
      (node (ref "GPS") (pin "17_SCL2") (pinfunction "17_SCL2_17_SCL2") (pintype "bidirectional"))
    )
    (net (code "76") (name "unconnected-(GPS-Pad18_RESERVED)") (class "Default")
      (node (ref "GPS") (pin "18_RESERVED") (pinfunction "18_RESERVED_18_RESERVED") (pintype "bidirectional"))
    )
    (net (code "77") (name "unconnected-(IC2-DC-Pad4)") (class "Default")
      (node (ref "IC2") (pin "4") (pinfunction "DC_4") (pintype "input"))
    )
    (net (code "78") (name "unconnected-(JTAG1-Pad7)") (class "Default")
      (node (ref "JTAG1") (pin "7") (pinfunction "7_7") (pintype "passive"))
    )
    (net (code "79") (name "unconnected-(LOW-G_ACC-NC-Pad10)") (class "Default")
      (node (ref "LOW-G_ACC") (pin "10") (pinfunction "NC_10") (pintype "bidirectional"))
    )
    (net (code "80") (name "unconnected-(U1D-PB12-Pad33)") (class "Default")
      (node (ref "U1") (pin "33") (pinfunction "PB12_33") (pintype "bidirectional"))
    )
    (net (code "81") (name "unconnected-(U1E-PB0-Pad26)") (class "Default")
      (node (ref "U1") (pin "26") (pinfunction "PB0_26") (pintype "bidirectional"))
    )
    (net (code "82") (name "unconnected-(U1E-PB1-Pad27)") (class "Default")
      (node (ref "U1") (pin "27") (pinfunction "PB1_27") (pintype "bidirectional"))
    )
    (net (code "83") (name "unconnected-(U1F-PC14-Pad3)") (class "Default")
      (node (ref "U1") (pin "3") (pinfunction "PC14_3") (pintype "bidirectional"))
    )
    (net (code "84") (name "unconnected-(U1F-PC15-Pad4)") (class "Default")
      (node (ref "U1") (pin "4") (pinfunction "PC15_4") (pintype "bidirectional"))
    )
    (net (code "85") (name "unconnected-(X1-Pad4)") (class "Default")
      (node (ref "X1") (pin "4") (pinfunction "4_4") (pintype "input"))
    )
    (net (code "86") (name "unconnected-(XB1-AD0{slash}DIO0-PadP$20)") (class "Default")
      (node (ref "XB1") (pin "P$20") (pinfunction "AD0/DIO0_P$20") (pintype "bidirectional"))
    )
    (net (code "87") (name "unconnected-(XB1-AD1{slash}DIO1-PadP$19)") (class "Default")
      (node (ref "XB1") (pin "P$19") (pinfunction "AD1/DIO1_P$19") (pintype "bidirectional"))
    )
    (net (code "88") (name "unconnected-(XB1-AD2{slash}DIO2-PadP$18)") (class "Default")
      (node (ref "XB1") (pin "P$18") (pinfunction "AD2/DIO2_P$18") (pintype "bidirectional"))
    )
    (net (code "89") (name "unconnected-(XB1-ASSOC{slash}AD5{slash}DIO5-PadP$15)") (class "Default")
      (node (ref "XB1") (pin "P$15") (pinfunction "ASSOC/AD5/DIO5_P$15") (pintype "bidirectional"))
    )
    (net (code "90") (name "unconnected-(XB1-CD{slash}DOUT_EN{slash}DO8-PadP$4)") (class "Default")
      (node (ref "XB1") (pin "P$4") (pinfunction "CD/DOUT_EN/DO8_P$4") (pintype "output"))
    )
    (net (code "91") (name "unconnected-(XB1-COORD_SEL{slash}AD3{slash}DIO3-PadP$17)") (class "Default")
      (node (ref "XB1") (pin "P$17") (pinfunction "COORD_SEL/AD3/DIO3_P$17") (pintype "bidirectional"))
    )
    (net (code "92") (name "unconnected-(XB1-ON{slash}~{SLEEP}-PadP$13)") (class "Default")
      (node (ref "XB1") (pin "P$13") (pinfunction "ON/~{SLEEP}_P$13") (pintype "output"))
    )
    (net (code "93") (name "unconnected-(XB1-PWM0{slash}RSSI-PadP$6)") (class "Default")
      (node (ref "XB1") (pin "P$6") (pinfunction "PWM0/RSSI_P$6") (pintype "output"))
    )
    (net (code "94") (name "unconnected-(XB1-RF_TX{slash}AD4{slash}DIO4-PadP$11)") (class "Default")
      (node (ref "XB1") (pin "P$11") (pinfunction "RF_TX/AD4/DIO4_P$11") (pintype "bidirectional"))
    )
    (net (code "95") (name "unconnected-(XB1-~{CTS}{slash}DIO7-PadP$12)") (class "Default")
      (node (ref "XB1") (pin "P$12") (pinfunction "~{CTS}/DIO7_P$12") (pintype "bidirectional"))
    )
    (net (code "96") (name "unconnected-(XB1-~{DTR}{slash}SLEEP_RQ{slash}DI8-PadP$9)") (class "Default")
      (node (ref "XB1") (pin "P$9") (pinfunction "~{DTR}/SLEEP_RQ/DI8_P$9") (pintype "bidirectional"))
    )
    (net (code "97") (name "unconnected-(XB1-~{RESET}-PadP$5)") (class "Default")
      (node (ref "XB1") (pin "P$5") (pinfunction "~{RESET}_P$5") (pintype "input"))
    )
    (net (code "98") (name "unconnected-(XB1-~{RTS}{slash}AD6{slash}DIO6-PadP$16)") (class "Default")
      (node (ref "XB1") (pin "P$16") (pinfunction "~{RTS}/AD6/DIO6_P$16") (pintype "bidirectional"))
    )
  )
)
